# schematic.net
KiCad netlist of a schematic drawn in EasyEDA
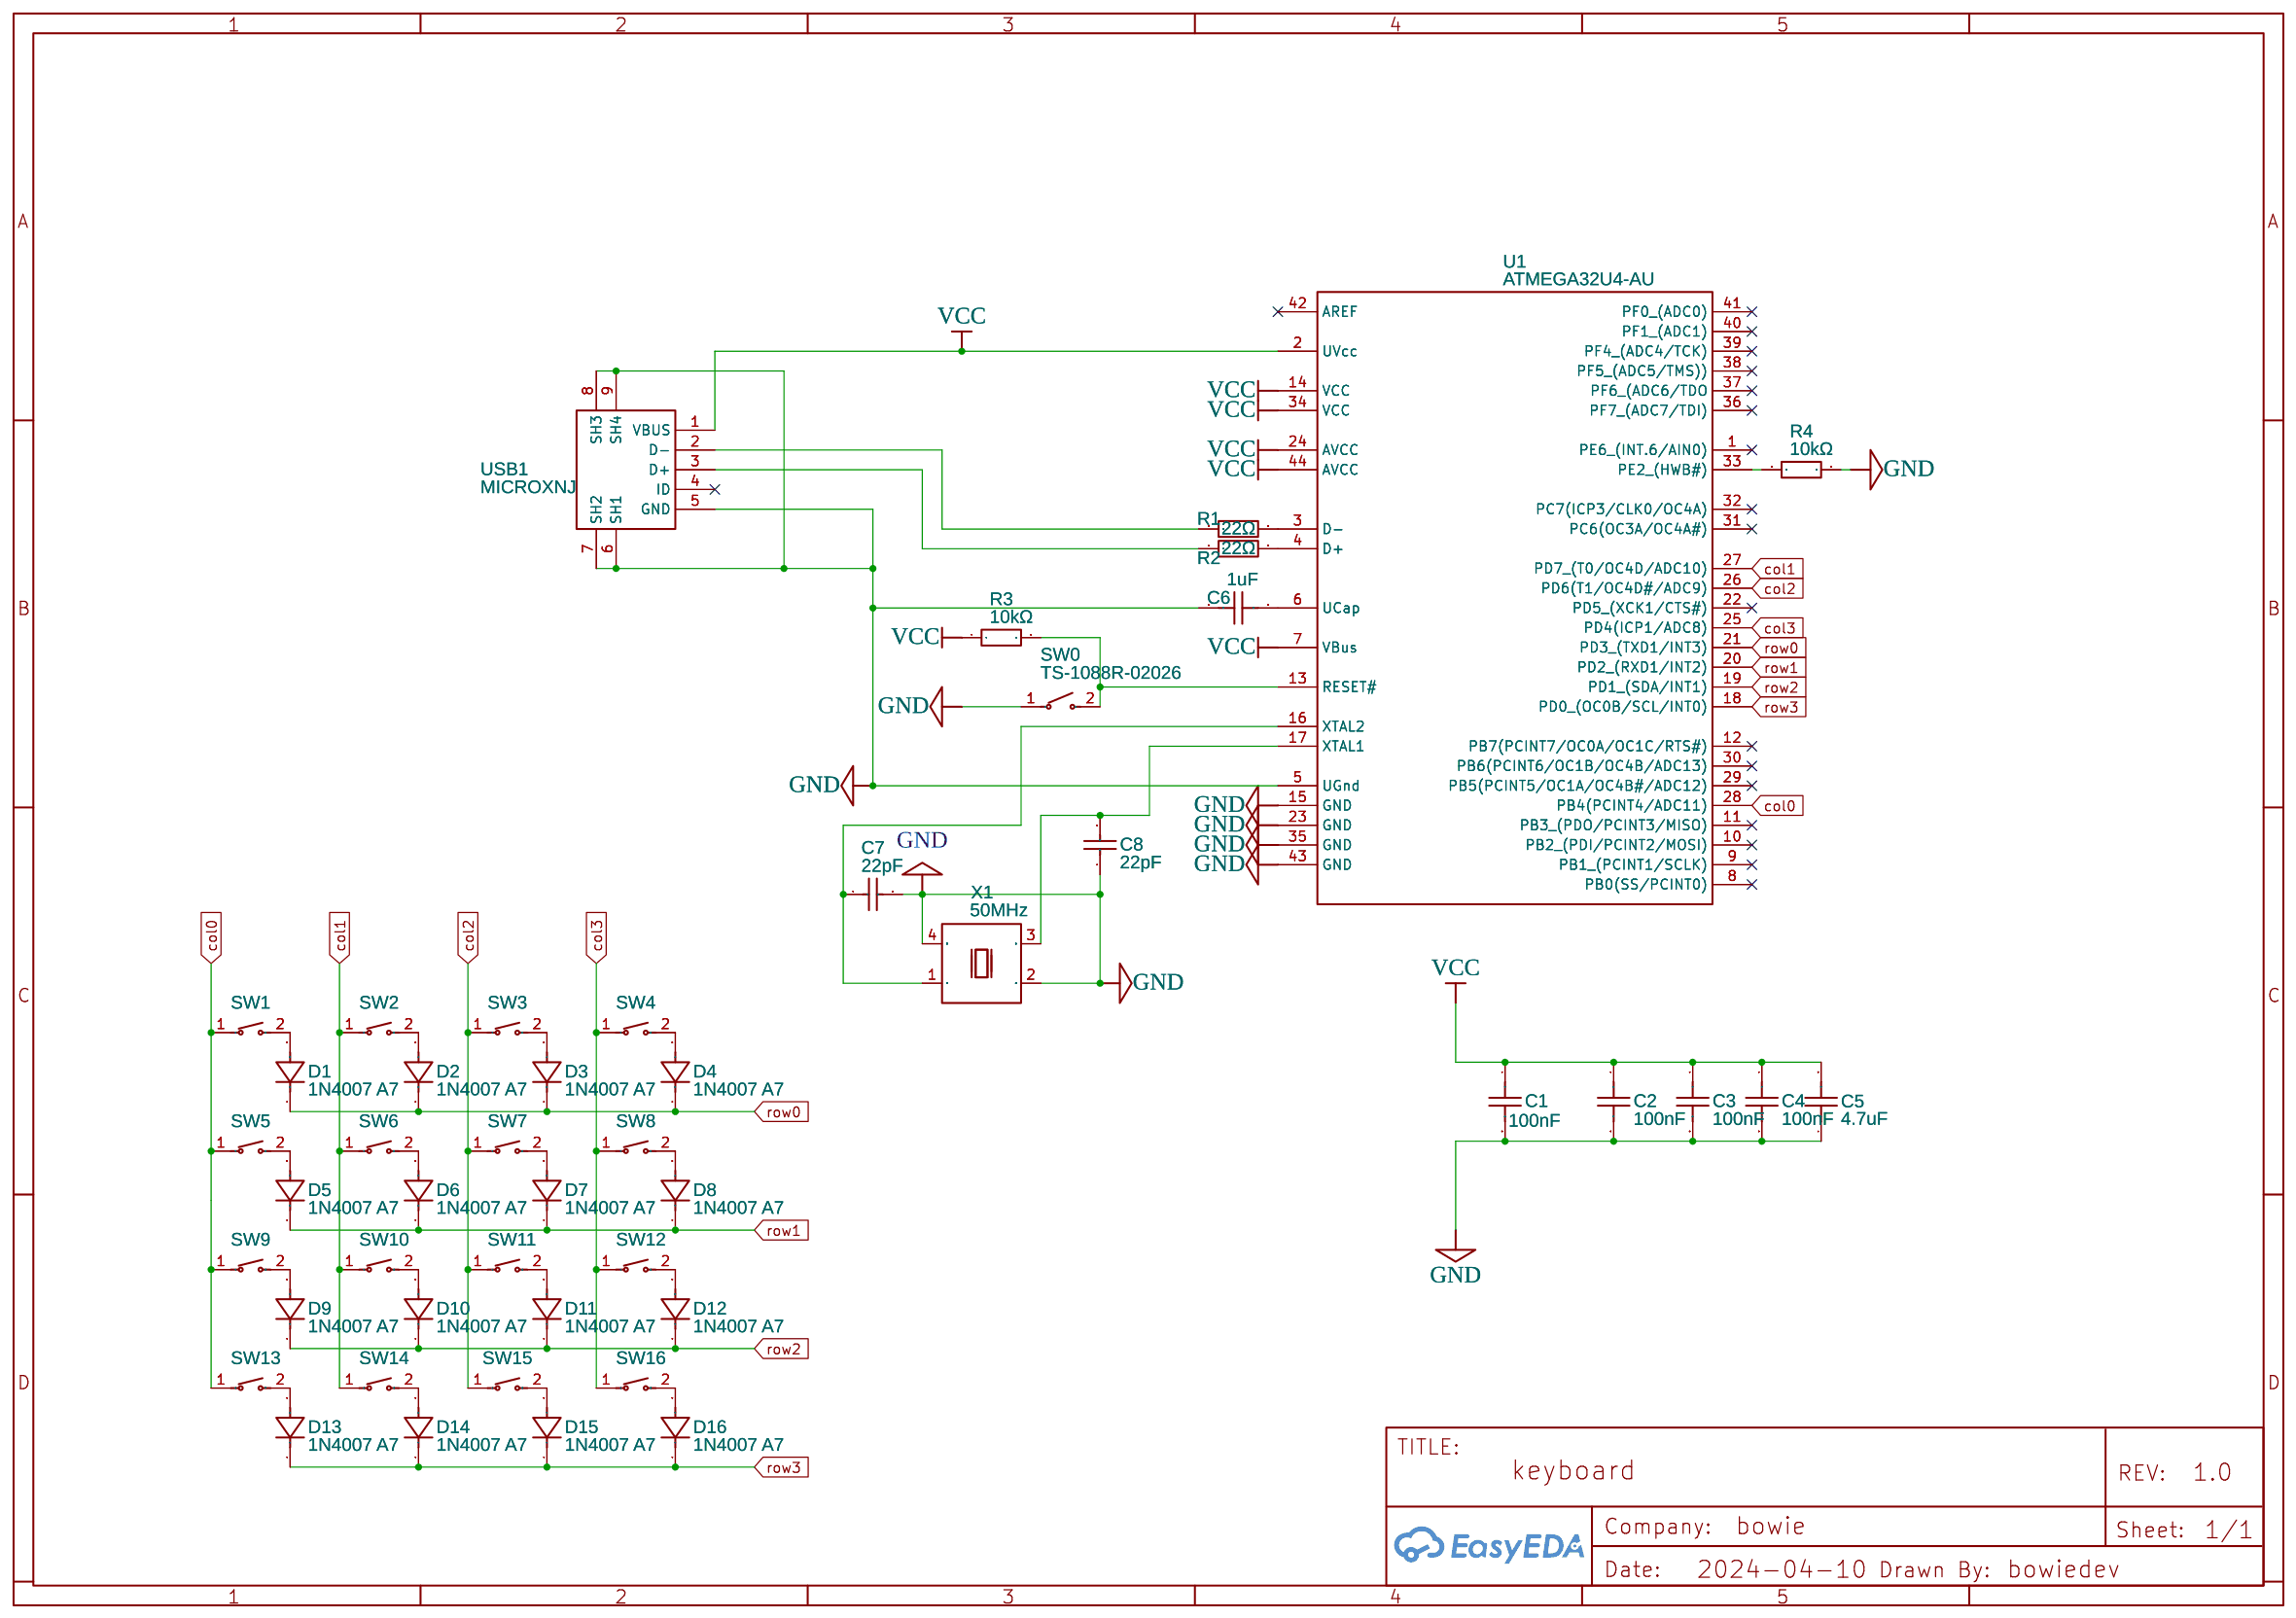
[diagram p0: schematic sheet]

(export (version "E")
  (design (tool "Eeschema 10.0.6"))
  (components
    (comp (ref "C1")
      (value "100nF")
      (fields (field (name "Manufacturer Part") "C1005X7R1C104KT000F") (field (name "Manufacturer") "TDK"))
      (libsource (lib "") (part "C1005X7R1C104KT000F"))
    )
    (comp (ref "C2")
      (value "100nF")
      (fields (field (name "Manufacturer Part") "C1005X7R1C104KT000F") (field (name "Manufacturer") "TDK"))
      (libsource (lib "") (part "C1005X7R1C104KT000F"))
    )
    (comp (ref "C3")
      (value "100nF")
      (fields (field (name "Manufacturer Part") "C1005X7R1C104KT000F") (field (name "Manufacturer") "TDK"))
      (libsource (lib "") (part "C1005X7R1C104KT000F"))
    )
    (comp (ref "C4")
      (value "100nF")
      (fields (field (name "Manufacturer Part") "C1005X7R1C104KT000F") (field (name "Manufacturer") "TDK"))
      (libsource (lib "") (part "C1005X7R1C104KT000F"))
    )
    (comp (ref "C5")
      (value "4.7uF")
      (fields
        (field (name "Manufacturer Part") "CS2012X5R475K500NRE")
        (field (name "Manufacturer") "SAMWHA(三和)")
      )
      (libsource (lib "") (part "CS2012X5R475K500NRE"))
    )
    (comp (ref "C6")
      (value "1uF")
      (fields
        (field (name "Manufacturer Part") "CS1608X7R105K250NRB")
        (field (name "Manufacturer") "SAMWHA(三和)")
      )
      (libsource (lib "") (part "CS1608X7R105K250NRB"))
    )
    (comp (ref "C7")
      (value "22pF")
      (fields (field (name "Manufacturer Part") "0402CG220J500NT") (field (name "Manufacturer") "FH(风华)"))
      (libsource (lib "") (part "0402CG220J500NT_1"))
    )
    (comp (ref "C8")
      (value "22pF")
      (fields (field (name "Manufacturer Part") "0402CG220J500NT") (field (name "Manufacturer") "FH(风华)"))
      (libsource (lib "") (part "0402CG220J500NT"))
    )
    (comp (ref "D1")
      (value "1N4007 A7")
      (fields (field (name "Manufacturer") "MSKSEMI(美森科)"))
      (libsource (lib "") (part "1N4007 A7"))
    )
    (comp (ref "D2")
      (value "1N4007 A7")
      (fields (field (name "Manufacturer") "MSKSEMI(美森科)"))
      (libsource (lib "") (part "1N4007 A7"))
    )
    (comp (ref "D3")
      (value "1N4007 A7")
      (fields (field (name "Manufacturer") "MSKSEMI(美森科)"))
      (libsource (lib "") (part "1N4007 A7"))
    )
    (comp (ref "D4")
      (value "1N4007 A7")
      (fields (field (name "Manufacturer") "MSKSEMI(美森科)"))
      (libsource (lib "") (part "1N4007 A7"))
    )
    (comp (ref "D5")
      (value "1N4007 A7")
      (fields (field (name "Manufacturer") "MSKSEMI(美森科)"))
      (libsource (lib "") (part "1N4007 A7"))
    )
    (comp (ref "D6")
      (value "1N4007 A7")
      (fields (field (name "Manufacturer") "MSKSEMI(美森科)"))
      (libsource (lib "") (part "1N4007 A7"))
    )
    (comp (ref "D7")
      (value "1N4007 A7")
      (fields (field (name "Manufacturer") "MSKSEMI(美森科)"))
      (libsource (lib "") (part "1N4007 A7"))
    )
    (comp (ref "D8")
      (value "1N4007 A7")
      (fields (field (name "Manufacturer") "MSKSEMI(美森科)"))
      (libsource (lib "") (part "1N4007 A7"))
    )
    (comp (ref "D9")
      (value "1N4007 A7")
      (fields (field (name "Manufacturer") "MSKSEMI(美森科)"))
      (libsource (lib "") (part "1N4007 A7"))
    )
    (comp (ref "D10")
      (value "1N4007 A7")
      (fields (field (name "Manufacturer") "MSKSEMI(美森科)"))
      (libsource (lib "") (part "1N4007 A7"))
    )
    (comp (ref "D11")
      (value "1N4007 A7")
      (fields (field (name "Manufacturer") "MSKSEMI(美森科)"))
      (libsource (lib "") (part "1N4007 A7"))
    )
    (comp (ref "D12")
      (value "1N4007 A7")
      (fields (field (name "Manufacturer") "MSKSEMI(美森科)"))
      (libsource (lib "") (part "1N4007 A7"))
    )
    (comp (ref "D13")
      (value "1N4007 A7")
      (fields (field (name "Manufacturer") "MSKSEMI(美森科)"))
      (libsource (lib "") (part "1N4007 A7"))
    )
    (comp (ref "D14")
      (value "1N4007 A7")
      (fields (field (name "Manufacturer") "MSKSEMI(美森科)"))
      (libsource (lib "") (part "1N4007 A7"))
    )
    (comp (ref "D15")
      (value "1N4007 A7")
      (fields (field (name "Manufacturer") "MSKSEMI(美森科)"))
      (libsource (lib "") (part "1N4007 A7"))
    )
    (comp (ref "D16")
      (value "1N4007 A7")
      (fields (field (name "Manufacturer") "MSKSEMI(美森科)"))
      (libsource (lib "") (part "1N4007 A7"))
    )
    (comp (ref "R1")
      (value "22Ω")
      (fields
        (field (name "Manufacturer Part") "0805W8J0220T5E")
        (field (name "Manufacturer") "UNI-ROYAL(厚声)")
      )
      (libsource (lib "") (part "0805W8J0220T5E"))
    )
    (comp (ref "R2")
      (value "22Ω")
      (fields
        (field (name "Manufacturer Part") "0805W8J0220T5E")
        (field (name "Manufacturer") "UNI-ROYAL(厚声)")
      )
      (libsource (lib "") (part "0805W8J0220T5E"))
    )
    (comp (ref "R3")
      (value "10kΩ")
      (fields
        (field (name "Manufacturer Part") "0805W8F1002T5E")
        (field (name "Manufacturer") "UNI-ROYAL(厚声)")
      )
      (libsource (lib "") (part "0805W8F1002T5E"))
    )
    (comp (ref "R4")
      (value "10kΩ")
      (fields
        (field (name "Manufacturer Part") "0805W8F1002T5E")
        (field (name "Manufacturer") "UNI-ROYAL(厚声)")
      )
      (libsource (lib "") (part "0805W8F1002T5E"))
    )
    (comp (ref "SW0")
      (value "TS-1088R-02026")
      (fields (field (name "Manufacturer") "XUNPU(讯普)"))
      (libsource (lib "") (part "TS-1088R-02026"))
    )
    (comp (ref "SW1")
      (value "CPG151101D93")
      (fields (field (name "Manufacturer") "Kailh(凯华)"))
      (libsource (lib "") (part "CPG151101D93"))
    )
    (comp (ref "SW2")
      (value "CPG151101D93")
      (fields (field (name "Manufacturer") "Kailh(凯华)"))
      (libsource (lib "") (part "CPG151101D93"))
    )
    (comp (ref "SW3")
      (value "CPG151101D93")
      (fields (field (name "Manufacturer") "Kailh(凯华)"))
      (libsource (lib "") (part "CPG151101D93"))
    )
    (comp (ref "SW4")
      (value "CPG151101D93")
      (fields (field (name "Manufacturer") "Kailh(凯华)"))
      (libsource (lib "") (part "CPG151101D93"))
    )
    (comp (ref "SW5")
      (value "CPG151101D93")
      (fields (field (name "Manufacturer") "Kailh(凯华)"))
      (libsource (lib "") (part "CPG151101D93"))
    )
    (comp (ref "SW6")
      (value "CPG151101D93")
      (fields (field (name "Manufacturer") "Kailh(凯华)"))
      (libsource (lib "") (part "CPG151101D93"))
    )
    (comp (ref "SW7")
      (value "CPG151101D93")
      (fields (field (name "Manufacturer") "Kailh(凯华)"))
      (libsource (lib "") (part "CPG151101D93"))
    )
    (comp (ref "SW8")
      (value "CPG151101D93")
      (fields (field (name "Manufacturer") "Kailh(凯华)"))
      (libsource (lib "") (part "CPG151101D93"))
    )
    (comp (ref "SW9")
      (value "CPG151101D93")
      (fields (field (name "Manufacturer") "Kailh(凯华)"))
      (libsource (lib "") (part "CPG151101D93"))
    )
    (comp (ref "SW10")
      (value "CPG151101D93")
      (fields (field (name "Manufacturer") "Kailh(凯华)"))
      (libsource (lib "") (part "CPG151101D93"))
    )
    (comp (ref "SW11")
      (value "CPG151101D93")
      (fields (field (name "Manufacturer") "Kailh(凯华)"))
      (libsource (lib "") (part "CPG151101D93"))
    )
    (comp (ref "SW12")
      (value "CPG151101D93")
      (fields (field (name "Manufacturer") "Kailh(凯华)"))
      (libsource (lib "") (part "CPG151101D93"))
    )
    (comp (ref "SW13")
      (value "CPG151101D93")
      (fields (field (name "Manufacturer") "Kailh(凯华)"))
      (libsource (lib "") (part "CPG151101D93"))
    )
    (comp (ref "SW14")
      (value "CPG151101D93")
      (fields (field (name "Manufacturer") "Kailh(凯华)"))
      (libsource (lib "") (part "CPG151101D93"))
    )
    (comp (ref "SW15")
      (value "CPG151101D93")
      (fields (field (name "Manufacturer") "Kailh(凯华)"))
      (libsource (lib "") (part "CPG151101D93"))
    )
    (comp (ref "SW16")
      (value "CPG151101D93")
      (fields (field (name "Manufacturer") "Kailh(凯华)"))
      (libsource (lib "") (part "CPG151101D93"))
    )
    (comp (ref "U1")
      (value "ATMEGA32U4-AU")
      (fields (field (name "Manufacturer") "MICROCHIP(美国微芯)"))
      (libsource (lib "") (part "ATMEGA32U4-AU"))
    )
    (comp (ref "USB1")
      (value "MICROXNJ")
      (fields (field (name "Manufacturer Part") "MicroXNJ") (field (name "Manufacturer") "SHOU HAN(首韩)"))
      (libsource (lib "") (part "MICROXNJ"))
    )
    (comp (ref "X1")
      (value "50MHz")
      (fields
        (field (name "Manufacturer Part") "OVETGLJTNF-50MHZ")
        (field (name "Manufacturer") "TAITIEN(泰艺电子)")
      )
      (libsource (lib "") (part "OVETGLJTNF-50MHZ"))
    )
  )
  (nets
    (net (code "1") (name "GND") (class "Default")
      (node (ref "C1") (pin "2") (pinfunction "2_2") (pintype "unspecified"))
      (node (ref "C2") (pin "2") (pinfunction "2_2") (pintype "unspecified"))
      (node (ref "C3") (pin "2") (pinfunction "2_2") (pintype "unspecified"))
      (node (ref "C4") (pin "2") (pinfunction "2_2") (pintype "unspecified"))
      (node (ref "C5") (pin "1") (pinfunction "1_1") (pintype "unspecified"))
      (node (ref "C6") (pin "1") (pinfunction "1_1") (pintype "unspecified"))
      (node (ref "C7") (pin "2") (pinfunction "2_2") (pintype "input"))
      (node (ref "C8") (pin "1") (pinfunction "1_1") (pintype "input"))
      (node (ref "R4") (pin "2") (pinfunction "2_2") (pintype "input"))
      (node (ref "SW0") (pin "1") (pinfunction "1_1") (pintype "unspecified"))
      (node (ref "U1") (pin "15") (pinfunction "GND_15") (pintype "passive"))
      (node (ref "U1") (pin "23") (pinfunction "GND_23") (pintype "passive"))
      (node (ref "U1") (pin "35") (pinfunction "GND_35") (pintype "passive"))
      (node (ref "U1") (pin "43") (pinfunction "GND_43") (pintype "passive"))
      (node (ref "U1") (pin "5") (pinfunction "UGnd_5") (pintype "passive"))
      (node (ref "USB1") (pin "5") (pinfunction "GND_5") (pintype "unspecified"))
      (node (ref "USB1") (pin "6") (pinfunction "SH1_6") (pintype "unspecified"))
      (node (ref "USB1") (pin "7") (pinfunction "SH2_7") (pintype "unspecified"))
      (node (ref "USB1") (pin "8") (pinfunction "SH3_8") (pintype "unspecified"))
      (node (ref "USB1") (pin "9") (pinfunction "SH4_9") (pintype "unspecified"))
      (node (ref "X1") (pin "2") (pinfunction "GND_2") (pintype "unspecified"))
      (node (ref "X1") (pin "4") (pinfunction "VCC_4") (pintype "unspecified"))
    )
    (net (code "2") (name "Net-(D1-A)") (class "Default")
      (node (ref "D1") (pin "2") (pinfunction "A_2") (pintype "unspecified"))
      (node (ref "SW1") (pin "2") (pinfunction "2_2") (pintype "unspecified"))
    )
    (net (code "3") (name "Net-(D2-A)") (class "Default")
      (node (ref "D2") (pin "2") (pinfunction "A_2") (pintype "unspecified"))
      (node (ref "SW2") (pin "2") (pinfunction "2_2") (pintype "unspecified"))
    )
    (net (code "4") (name "Net-(D3-A)") (class "Default")
      (node (ref "D3") (pin "2") (pinfunction "A_2") (pintype "unspecified"))
      (node (ref "SW3") (pin "2") (pinfunction "2_2") (pintype "unspecified"))
    )
    (net (code "5") (name "Net-(D4-A)") (class "Default")
      (node (ref "D4") (pin "2") (pinfunction "A_2") (pintype "unspecified"))
      (node (ref "SW4") (pin "2") (pinfunction "2_2") (pintype "unspecified"))
    )
    (net (code "6") (name "Net-(D5-A)") (class "Default")
      (node (ref "D5") (pin "2") (pinfunction "A_2") (pintype "unspecified"))
      (node (ref "SW5") (pin "2") (pinfunction "2_2") (pintype "unspecified"))
    )
    (net (code "7") (name "Net-(D6-A)") (class "Default")
      (node (ref "D6") (pin "2") (pinfunction "A_2") (pintype "unspecified"))
      (node (ref "SW6") (pin "2") (pinfunction "2_2") (pintype "unspecified"))
    )
    (net (code "8") (name "Net-(D7-A)") (class "Default")
      (node (ref "D7") (pin "2") (pinfunction "A_2") (pintype "unspecified"))
      (node (ref "SW7") (pin "2") (pinfunction "2_2") (pintype "unspecified"))
    )
    (net (code "9") (name "Net-(D8-A)") (class "Default")
      (node (ref "D8") (pin "2") (pinfunction "A_2") (pintype "unspecified"))
      (node (ref "SW8") (pin "2") (pinfunction "2_2") (pintype "unspecified"))
    )
    (net (code "10") (name "Net-(D9-A)") (class "Default")
      (node (ref "D9") (pin "2") (pinfunction "A_2") (pintype "unspecified"))
      (node (ref "SW9") (pin "2") (pinfunction "2_2") (pintype "unspecified"))
    )
    (net (code "11") (name "Net-(D10-A)") (class "Default")
      (node (ref "D10") (pin "2") (pinfunction "A_2") (pintype "unspecified"))
      (node (ref "SW10") (pin "2") (pinfunction "2_2") (pintype "unspecified"))
    )
    (net (code "12") (name "Net-(D11-A)") (class "Default")
      (node (ref "D11") (pin "2") (pinfunction "A_2") (pintype "unspecified"))
      (node (ref "SW11") (pin "2") (pinfunction "2_2") (pintype "unspecified"))
    )
    (net (code "13") (name "Net-(D12-A)") (class "Default")
      (node (ref "D12") (pin "2") (pinfunction "A_2") (pintype "unspecified"))
      (node (ref "SW12") (pin "2") (pinfunction "2_2") (pintype "unspecified"))
    )
    (net (code "14") (name "Net-(D13-A)") (class "Default")
      (node (ref "D13") (pin "2") (pinfunction "A_2") (pintype "unspecified"))
      (node (ref "SW13") (pin "2") (pinfunction "2_2") (pintype "unspecified"))
    )
    (net (code "15") (name "Net-(D14-A)") (class "Default")
      (node (ref "D14") (pin "2") (pinfunction "A_2") (pintype "unspecified"))
      (node (ref "SW14") (pin "2") (pinfunction "2_2") (pintype "unspecified"))
    )
    (net (code "16") (name "Net-(D15-A)") (class "Default")
      (node (ref "D15") (pin "2") (pinfunction "A_2") (pintype "unspecified"))
      (node (ref "SW15") (pin "2") (pinfunction "2_2") (pintype "unspecified"))
    )
    (net (code "17") (name "Net-(D16-A)") (class "Default")
      (node (ref "D16") (pin "2") (pinfunction "A_2") (pintype "unspecified"))
      (node (ref "SW16") (pin "2") (pinfunction "2_2") (pintype "unspecified"))
    )
    (net (code "18") (name "Net-(U1-D+)") (class "Default")
      (node (ref "R2") (pin "2") (pinfunction "2_2") (pintype "input"))
      (node (ref "U1") (pin "4") (pinfunction "D+_4") (pintype "bidirectional"))
    )
    (net (code "19") (name "Net-(U1-D-)") (class "Default")
      (node (ref "R1") (pin "2") (pinfunction "2_2") (pintype "input"))
      (node (ref "U1") (pin "3") (pinfunction "D-_3") (pintype "bidirectional"))
    )
    (net (code "20") (name "Net-(U1-PE2_(HWB#))") (class "Default")
      (node (ref "R4") (pin "1") (pinfunction "1_1") (pintype "input"))
      (node (ref "U1") (pin "33") (pinfunction "PE2_(HWB#)_33") (pintype "bidirectional"))
    )
    (net (code "21") (name "Net-(U1-RESET#)") (class "Default")
      (node (ref "R3") (pin "2") (pinfunction "2_2") (pintype "input"))
      (node (ref "SW0") (pin "2") (pinfunction "2_2") (pintype "unspecified"))
      (node (ref "U1") (pin "13") (pinfunction "RESET#_13") (pintype "unspecified"))
    )
    (net (code "22") (name "Net-(U1-UCap)") (class "Default")
      (node (ref "C6") (pin "2") (pinfunction "2_2") (pintype "unspecified"))
      (node (ref "U1") (pin "6") (pinfunction "UCap_6") (pintype "unspecified"))
    )
    (net (code "23") (name "Net-(U1-XTAL1)") (class "Default")
      (node (ref "C8") (pin "2") (pinfunction "2_2") (pintype "input"))
      (node (ref "U1") (pin "17") (pinfunction "XTAL1_17") (pintype "unspecified"))
      (node (ref "X1") (pin "3") (pinfunction "OUT_3") (pintype "unspecified"))
    )
    (net (code "24") (name "Net-(U1-XTAL2)") (class "Default")
      (node (ref "C7") (pin "1") (pinfunction "1_1") (pintype "input"))
      (node (ref "U1") (pin "16") (pinfunction "XTAL2_16") (pintype "output"))
      (node (ref "X1") (pin "1") (pinfunction "tri_1") (pintype "unspecified"))
    )
    (net (code "25") (name "Net-(USB1-D+)") (class "Default")
      (node (ref "R2") (pin "1") (pinfunction "1_1") (pintype "input"))
      (node (ref "USB1") (pin "3") (pinfunction "D+_3") (pintype "unspecified"))
    )
    (net (code "26") (name "Net-(USB1-D-)") (class "Default")
      (node (ref "R1") (pin "1") (pinfunction "1_1") (pintype "input"))
      (node (ref "USB1") (pin "2") (pinfunction "D-_2") (pintype "unspecified"))
    )
    (net (code "27") (name "VCC") (class "Default")
      (node (ref "C1") (pin "1") (pinfunction "1_1") (pintype "unspecified"))
      (node (ref "C2") (pin "1") (pinfunction "1_1") (pintype "unspecified"))
      (node (ref "C3") (pin "1") (pinfunction "1_1") (pintype "unspecified"))
      (node (ref "C4") (pin "1") (pinfunction "1_1") (pintype "unspecified"))
      (node (ref "C5") (pin "2") (pinfunction "2_2") (pintype "unspecified"))
      (node (ref "R3") (pin "1") (pinfunction "1_1") (pintype "input"))
      (node (ref "U1") (pin "14") (pinfunction "VCC_14") (pintype "passive"))
      (node (ref "U1") (pin "2") (pinfunction "UVcc_2") (pintype "passive"))
      (node (ref "U1") (pin "24") (pinfunction "AVCC_24") (pintype "passive"))
      (node (ref "U1") (pin "34") (pinfunction "VCC_34") (pintype "passive"))
      (node (ref "U1") (pin "44") (pinfunction "AVCC_44") (pintype "passive"))
      (node (ref "U1") (pin "7") (pinfunction "VBus_7") (pintype "unspecified"))
      (node (ref "USB1") (pin "1") (pinfunction "VBUS_1") (pintype "unspecified"))
    )
    (net (code "28") (name "col0") (class "Default")
      (node (ref "SW1") (pin "1") (pinfunction "1_1") (pintype "unspecified"))
      (node (ref "SW13") (pin "1") (pinfunction "1_1") (pintype "unspecified"))
      (node (ref "SW5") (pin "1") (pinfunction "1_1") (pintype "unspecified"))
      (node (ref "SW9") (pin "1") (pinfunction "1_1") (pintype "unspecified"))
      (node (ref "U1") (pin "28") (pinfunction "PB4(PCINT4/ADC11)_28") (pintype "bidirectional"))
    )
    (net (code "29") (name "col1") (class "Default")
      (node (ref "SW10") (pin "1") (pinfunction "1_1") (pintype "unspecified"))
      (node (ref "SW14") (pin "1") (pinfunction "1_1") (pintype "unspecified"))
      (node (ref "SW2") (pin "1") (pinfunction "1_1") (pintype "unspecified"))
      (node (ref "SW6") (pin "1") (pinfunction "1_1") (pintype "unspecified"))
      (node (ref "U1") (pin "27") (pinfunction "PD7_(T0/OC4D/ADC10)_27") (pintype "bidirectional"))
    )
    (net (code "30") (name "col2") (class "Default")
      (node (ref "SW11") (pin "1") (pinfunction "1_1") (pintype "unspecified"))
      (node (ref "SW15") (pin "1") (pinfunction "1_1") (pintype "unspecified"))
      (node (ref "SW3") (pin "1") (pinfunction "1_1") (pintype "unspecified"))
      (node (ref "SW7") (pin "1") (pinfunction "1_1") (pintype "unspecified"))
      (node (ref "U1") (pin "26") (pinfunction "PD6(T1/OC4D#/ADC9)_26") (pintype "bidirectional"))
    )
    (net (code "31") (name "col3") (class "Default")
      (node (ref "SW12") (pin "1") (pinfunction "1_1") (pintype "unspecified"))
      (node (ref "SW16") (pin "1") (pinfunction "1_1") (pintype "unspecified"))
      (node (ref "SW4") (pin "1") (pinfunction "1_1") (pintype "unspecified"))
      (node (ref "SW8") (pin "1") (pinfunction "1_1") (pintype "unspecified"))
      (node (ref "U1") (pin "25") (pinfunction "PD4(ICP1/ADC8)_25") (pintype "bidirectional"))
    )
    (net (code "32") (name "row0") (class "Default")
      (node (ref "D1") (pin "1") (pinfunction "K_1") (pintype "unspecified"))
      (node (ref "D2") (pin "1") (pinfunction "K_1") (pintype "unspecified"))
      (node (ref "D3") (pin "1") (pinfunction "K_1") (pintype "unspecified"))
      (node (ref "D4") (pin "1") (pinfunction "K_1") (pintype "unspecified"))
      (node (ref "U1") (pin "21") (pinfunction "PD3_(TXD1/INT3)_21") (pintype "bidirectional"))
    )
    (net (code "33") (name "row1") (class "Default")
      (node (ref "D5") (pin "1") (pinfunction "K_1") (pintype "unspecified"))
      (node (ref "D6") (pin "1") (pinfunction "K_1") (pintype "unspecified"))
      (node (ref "D7") (pin "1") (pinfunction "K_1") (pintype "unspecified"))
      (node (ref "D8") (pin "1") (pinfunction "K_1") (pintype "unspecified"))
      (node (ref "U1") (pin "20") (pinfunction "PD2_(RXD1/INT2)_20") (pintype "bidirectional"))
    )
    (net (code "34") (name "row2") (class "Default")
      (node (ref "D10") (pin "1") (pinfunction "K_1") (pintype "unspecified"))
      (node (ref "D11") (pin "1") (pinfunction "K_1") (pintype "unspecified"))
      (node (ref "D12") (pin "1") (pinfunction "K_1") (pintype "unspecified"))
      (node (ref "D9") (pin "1") (pinfunction "K_1") (pintype "unspecified"))
      (node (ref "U1") (pin "19") (pinfunction "PD1_(SDA/INT1)_19") (pintype "bidirectional"))
    )
    (net (code "35") (name "row3") (class "Default")
      (node (ref "D13") (pin "1") (pinfunction "K_1") (pintype "unspecified"))
      (node (ref "D14") (pin "1") (pinfunction "K_1") (pintype "unspecified"))
      (node (ref "D15") (pin "1") (pinfunction "K_1") (pintype "unspecified"))
      (node (ref "D16") (pin "1") (pinfunction "K_1") (pintype "unspecified"))
      (node (ref "U1") (pin "18") (pinfunction "PD0_(OC0B/SCL/INT0)_18") (pintype "bidirectional"))
    )
    (net (code "36") (name "unconnected-(U1-AREF-Pad42)") (class "Default")
      (node (ref "U1") (pin "42") (pinfunction "AREF_42") (pintype "unspecified+no_connect"))
    )
    (net (code "37") (name "unconnected-(U1-PB0(SS{slash}PCINT0)-Pad8)") (class "Default")
      (node (ref "U1") (pin "8") (pinfunction "PB0(SS/PCINT0)_8") (pintype "bidirectional+no_connect"))
    )
    (net (code "38") (name "unconnected-(U1-PB1_(PCINT1{slash}SCLK)-Pad9)") (class "Default")
      (node (ref "U1") (pin "9") (pinfunction "PB1_(PCINT1/SCLK)_9") (pintype "bidirectional+no_connect"))
    )
    (net (code "39") (name "unconnected-(U1-PB2_(PDI{slash}PCINT2{slash}MOSI)-Pad10)") (class "Default")
      (node (ref "U1") (pin "10") (pinfunction "PB2_(PDI/PCINT2/MOSI)_10") (pintype "bidirectional+no_connect"))
    )
    (net (code "40") (name "unconnected-(U1-PB3_(PDO{slash}PCINT3{slash}MISO)-Pad11)") (class "Default")
      (node (ref "U1") (pin "11") (pinfunction "PB3_(PDO/PCINT3/MISO)_11") (pintype "bidirectional+no_connect"))
    )
    (net (code "41") (name "unconnected-(U1-PB5(PCINT5{slash}OC1A{slash}OC4B#{slash}ADC12)-Pad29)") (class "Default")
      (node (ref "U1") (pin "29") (pinfunction "PB5(PCINT5/OC1A/OC4B#/ADC12)_29") (pintype "bidirectional+no_connect"))
    )
    (net (code "42") (name "unconnected-(U1-PB6(PCINT6{slash}OC1B{slash}OC4B{slash}ADC13)-Pad30)") (class "Default")
      (node (ref "U1") (pin "30") (pinfunction "PB6(PCINT6/OC1B/OC4B/ADC13)_30") (pintype "bidirectional+no_connect"))
    )
    (net (code "43") (name "unconnected-(U1-PB7(PCINT7{slash}OC0A{slash}OC1C{slash}RTS#)-Pad12)") (class "Default")
      (node (ref "U1") (pin "12") (pinfunction "PB7(PCINT7/OC0A/OC1C/RTS#)_12") (pintype "bidirectional+no_connect"))
    )
    (net (code "44") (name "unconnected-(U1-PC6(OC3A{slash}OC4A#)-Pad31)") (class "Default")
      (node (ref "U1") (pin "31") (pinfunction "PC6(OC3A/OC4A#)_31") (pintype "bidirectional+no_connect"))
    )
    (net (code "45") (name "unconnected-(U1-PC7(ICP3{slash}CLK0{slash}OC4A)-Pad32)") (class "Default")
      (node (ref "U1") (pin "32") (pinfunction "PC7(ICP3/CLK0/OC4A)_32") (pintype "bidirectional+no_connect"))
    )
    (net (code "46") (name "unconnected-(U1-PD5_(XCK1{slash}CTS#)-Pad22)") (class "Default")
      (node (ref "U1") (pin "22") (pinfunction "PD5_(XCK1/CTS#)_22") (pintype "bidirectional+no_connect"))
    )
    (net (code "47") (name "unconnected-(U1-PE6_(INT.6{slash}AIN0)-Pad1)") (class "Default")
      (node (ref "U1") (pin "1") (pinfunction "PE6_(INT.6/AIN0)_1") (pintype "bidirectional+no_connect"))
    )
    (net (code "48") (name "unconnected-(U1-PF0_(ADC0)-Pad41)") (class "Default")
      (node (ref "U1") (pin "41") (pinfunction "PF0_(ADC0)_41") (pintype "bidirectional+no_connect"))
    )
    (net (code "49") (name "unconnected-(U1-PF1_(ADC1)-Pad40)") (class "Default")
      (node (ref "U1") (pin "40") (pinfunction "PF1_(ADC1)_40") (pintype "bidirectional+no_connect"))
    )
    (net (code "50") (name "unconnected-(U1-PF4_(ADC4{slash}TCK)-Pad39)") (class "Default")
      (node (ref "U1") (pin "39") (pinfunction "PF4_(ADC4/TCK)_39") (pintype "bidirectional+no_connect"))
    )
    (net (code "51") (name "unconnected-(U1-PF5_(ADC5{slash}TMS))-Pad38)") (class "Default")
      (node (ref "U1") (pin "38") (pinfunction "PF5_(ADC5/TMS))_38") (pintype "bidirectional+no_connect"))
    )
    (net (code "52") (name "unconnected-(U1-PF6_(ADC6{slash}TDO-Pad37)") (class "Default")
      (node (ref "U1") (pin "37") (pinfunction "PF6_(ADC6/TDO_37") (pintype "bidirectional+no_connect"))
    )
    (net (code "53") (name "unconnected-(U1-PF7_(ADC7{slash}TDI)-Pad36)") (class "Default")
      (node (ref "U1") (pin "36") (pinfunction "PF7_(ADC7/TDI)_36") (pintype "bidirectional+no_connect"))
    )
    (net (code "54") (name "unconnected-(USB1-ID-Pad4)") (class "Default")
      (node (ref "USB1") (pin "4") (pinfunction "ID_4") (pintype "unspecified+no_connect"))
    )
  )
)
